# Constant_Voltage_schematic_2022-05-03.net
KiCad netlist of a schematic drawn in Altium Designer
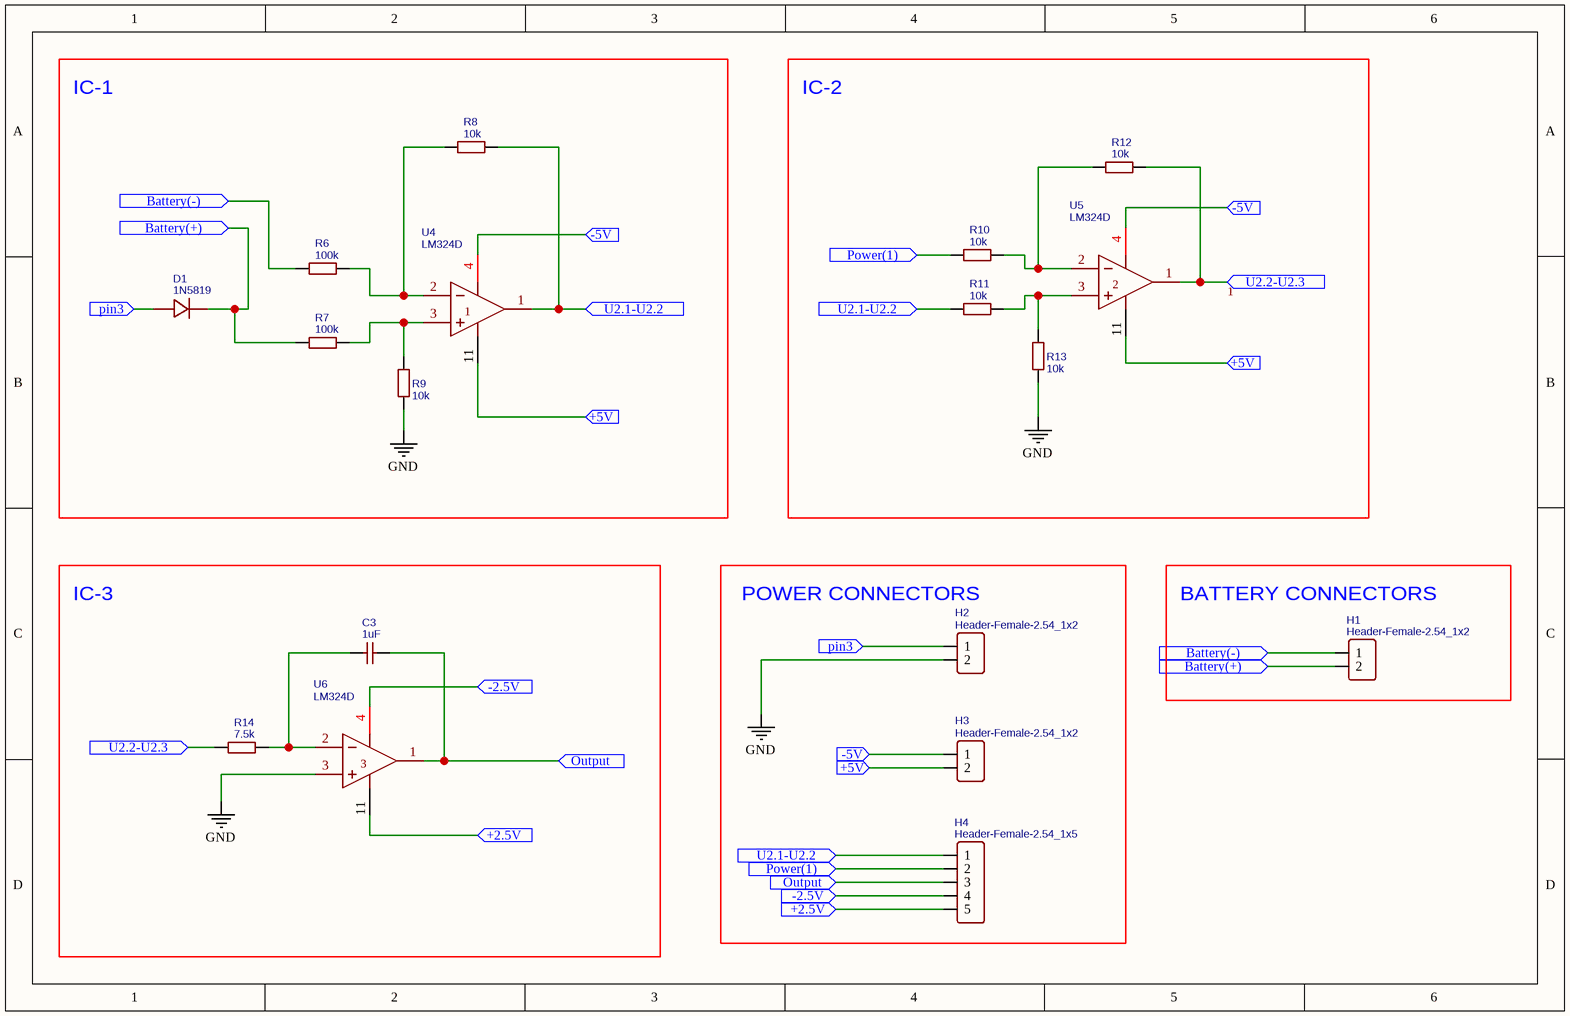
[diagram p0: Constant_Voltage_schematic_2022-05-03.schdoc]

(export (version "E")
  (design (tool "Eeschema 10.0.6"))
  (components
    (comp (ref "C3")
      (value "1uF")
      (fields
        (field (name "BOM_MANUFACTURER PART") "22pf/50V 10%")
        (field (name "BOM_SUPPLIER PART") "C9316")
      )
      (libsource (lib "altium-import") (part "root_0_1uF_"))
    )
    (comp (ref "D1")
      (value "1N5819")
      (fields (field (name "BOM_SUPPLIER PART") "C256527") (field (name "CONTRIBUTOR") "LCSC"))
      (libsource (lib "altium-import") (part "root_2_1N5819_"))
    )
    (comp (ref "H1")
      (value "Header-Female-2.54_1x2")
      (fields
        (field (name "BOM_MANUFACTURER PART") "2.54-1*2PFemale")
        (field (name "BOM_SUPPLIER PART") "C49661")
      )
      (libsource (lib "altium-import") (part "root_0_Header-Female-2.54_1x2_"))
    )
    (comp (ref "H2")
      (value "Header-Female-2.54_1x2")
      (fields
        (field (name "BOM_MANUFACTURER PART") "2.54-1*2PFemale")
        (field (name "BOM_SUPPLIER PART") "C49661")
      )
      (libsource (lib "altium-import") (part "root_0_Header-Female-2.54_1x2_"))
    )
    (comp (ref "H3")
      (value "Header-Female-2.54_1x2")
      (fields
        (field (name "BOM_MANUFACTURER PART") "2.54-1*2PFemale")
        (field (name "BOM_SUPPLIER PART") "C49661")
      )
      (libsource (lib "altium-import") (part "root_0_Header-Female-2.54_1x2_"))
    )
    (comp (ref "H4")
      (value "Header-Female-2.54_1x5")
      (fields
        (field (name "BOM_MANUFACTURER PART") "2.54mm 1*5p Female header")
        (field (name "BOM_SUPPLIER PART") "C50950")
      )
      (libsource (lib "altium-import") (part "root_0_Header-Female-2.54_1x5_"))
    )
    (comp (ref "R6")
      (value "100k")
      (fields
        (field (name "POWER") "1/4W")
        (field (name "TOLERANCE") "±1%")
        (field (name "BOM_SUPPLIER PART") "E57439")
      )
      (libsource (lib "altium-import") (part "root_0_100k_"))
    )
    (comp (ref "R7")
      (value "100k")
      (fields
        (field (name "POWER") "1/4W")
        (field (name "TOLERANCE") "±1%")
        (field (name "BOM_SUPPLIER PART") "E57439")
      )
      (libsource (lib "altium-import") (part "root_0_100k_"))
    )
    (comp (ref "R8")
      (value "10k")
      (fields
        (field (name "POWER") "1/4W")
        (field (name "TOLERANCE") "±1%")
        (field (name "BOM_SUPPLIER PART") "E57439")
      )
      (libsource (lib "altium-import") (part "root_0_10k_"))
    )
    (comp (ref "R9")
      (value "10k")
      (fields
        (field (name "POWER") "1/4W")
        (field (name "TOLERANCE") "±1%")
        (field (name "BOM_SUPPLIER PART") "E57439")
      )
      (libsource (lib "altium-import") (part "root_1_10k_"))
    )
    (comp (ref "R10")
      (value "10k")
      (fields
        (field (name "POWER") "1/4W")
        (field (name "TOLERANCE") "±1%")
        (field (name "BOM_SUPPLIER PART") "E57439")
      )
      (libsource (lib "altium-import") (part "root_0_10k_"))
    )
    (comp (ref "R11")
      (value "10k")
      (fields
        (field (name "POWER") "1/4W")
        (field (name "TOLERANCE") "±1%")
        (field (name "BOM_SUPPLIER PART") "E57439")
      )
      (libsource (lib "altium-import") (part "root_0_10k_"))
    )
    (comp (ref "R12")
      (value "10k")
      (fields
        (field (name "POWER") "1/4W")
        (field (name "TOLERANCE") "±1%")
        (field (name "BOM_SUPPLIER PART") "E57439")
      )
      (libsource (lib "altium-import") (part "root_0_10k_"))
    )
    (comp (ref "R13")
      (value "10k")
      (fields
        (field (name "POWER") "1/4W")
        (field (name "TOLERANCE") "±1%")
        (field (name "BOM_SUPPLIER PART") "E57439")
      )
      (libsource (lib "altium-import") (part "root_1_10k_"))
    )
    (comp (ref "R14")
      (value "7.5k")
      (fields
        (field (name "POWER") "1/4W")
        (field (name "TOLERANCE") "±1%")
        (field (name "BOM_SUPPLIER PART") "E57439")
      )
      (libsource (lib "altium-import") (part "root_0_7.5k_"))
    )
    (comp (ref "U4")
      (value "LM324D")
      (fields
        (field (name "BOM_SUPPLIER PART") "C2935189")
        (field (name "SUBPART_NO") "1")
        (field (name "CONTRIBUTOR") "LCSC")
      )
      (libsource (lib "altium-import") (part "root_0_LM324D_"))
    )
    (comp (ref "U5")
      (value "LM324D")
      (fields
        (field (name "BOM_SUPPLIER PART") "C2935189")
        (field (name "SUBPART_NO") "1")
        (field (name "CONTRIBUTOR") "LCSC")
      )
      (libsource (lib "altium-import") (part "root_0_LM324D_"))
    )
    (comp (ref "U6")
      (value "LM324D")
      (fields
        (field (name "BOM_SUPPLIER PART") "C2935189")
        (field (name "SUBPART_NO") "1")
        (field (name "CONTRIBUTOR") "LCSC")
      )
      (libsource (lib "altium-import") (part "root_0_LM324D_"))
    )
  )
  (nets
    (net (code "1") (name "/+2.5V") (class "Default")
      (node (ref "H4") (pin "5") (pinfunction "5_5") (pintype "passive"))
      (node (ref "U6") (pin "11") (pinfunction "VCC-_11") (pintype "passive"))
    )
    (net (code "2") (name "/+5V") (class "Default")
      (node (ref "H3") (pin "2") (pinfunction "2_2") (pintype "passive"))
      (node (ref "U4") (pin "11") (pinfunction "VCC-_11") (pintype "passive"))
      (node (ref "U5") (pin "11") (pinfunction "VCC-_11") (pintype "passive"))
    )
    (net (code "3") (name "/-2.5V") (class "Default")
      (node (ref "H4") (pin "4") (pinfunction "4_4") (pintype "passive"))
      (node (ref "U6") (pin "4") (pinfunction "VCC+_4") (pintype "passive"))
    )
    (net (code "4") (name "/-5V") (class "Default")
      (node (ref "H3") (pin "1") (pinfunction "1_1") (pintype "passive"))
      (node (ref "U4") (pin "4") (pinfunction "VCC+_4") (pintype "passive"))
      (node (ref "U5") (pin "4") (pinfunction "VCC+_4") (pintype "passive"))
    )
    (net (code "5") (name "/Battery(+)") (class "Default")
      (node (ref "D1") (pin "1") (pinfunction "K_1") (pintype "passive"))
      (node (ref "H1") (pin "2") (pinfunction "2_2") (pintype "passive"))
      (node (ref "R7") (pin "1") (pinfunction "1_1") (pintype "passive"))
    )
    (net (code "6") (name "/Battery(-)") (class "Default")
      (node (ref "H1") (pin "1") (pinfunction "1_1") (pintype "passive"))
      (node (ref "R6") (pin "1") (pinfunction "1_1") (pintype "passive"))
    )
    (net (code "7") (name "/Output") (class "Default")
      (node (ref "C3") (pin "2") (pinfunction "2_2") (pintype "passive"))
      (node (ref "H4") (pin "3") (pinfunction "3_3") (pintype "passive"))
      (node (ref "U6") (pin "1") (pinfunction "OUT1_1") (pintype "passive"))
    )
    (net (code "8") (name "/Power(1)") (class "Default")
      (node (ref "H4") (pin "2") (pinfunction "2_2") (pintype "passive"))
      (node (ref "R10") (pin "1") (pinfunction "1_1") (pintype "passive"))
    )
    (net (code "9") (name "/U2.1-U2.2") (class "Default")
      (node (ref "H4") (pin "1") (pinfunction "1_1") (pintype "passive"))
      (node (ref "R11") (pin "1") (pinfunction "1_1") (pintype "passive"))
      (node (ref "R8") (pin "2") (pinfunction "2_2") (pintype "passive"))
      (node (ref "U4") (pin "1") (pinfunction "OUT1_1") (pintype "passive"))
    )
    (net (code "10") (name "/U2.2-U2.3") (class "Default")
      (node (ref "R12") (pin "2") (pinfunction "2_2") (pintype "passive"))
      (node (ref "R14") (pin "1") (pinfunction "1_1") (pintype "passive"))
      (node (ref "U5") (pin "1") (pinfunction "OUT1_1") (pintype "passive"))
    )
    (net (code "11") (name "/pin3") (class "Default")
      (node (ref "D1") (pin "2") (pinfunction "A_2") (pintype "passive"))
      (node (ref "H2") (pin "1") (pinfunction "1_1") (pintype "passive"))
    )
    (net (code "12") (name "GND") (class "Default")
      (node (ref "H2") (pin "2") (pinfunction "2_2") (pintype "passive"))
      (node (ref "R13") (pin "1") (pinfunction "1_1") (pintype "passive"))
      (node (ref "R9") (pin "1") (pinfunction "1_1") (pintype "passive"))
      (node (ref "U6") (pin "3") (pinfunction "IN1+_3") (pintype "passive"))
    )
    (net (code "13") (name "Net-(U4-IN1+)") (class "Default")
      (node (ref "R7") (pin "2") (pinfunction "2_2") (pintype "passive"))
      (node (ref "R9") (pin "2") (pinfunction "2_2") (pintype "passive"))
      (node (ref "U4") (pin "3") (pinfunction "IN1+_3") (pintype "passive"))
    )
    (net (code "14") (name "Net-(U4-IN1-)") (class "Default")
      (node (ref "R6") (pin "2") (pinfunction "2_2") (pintype "passive"))
      (node (ref "R8") (pin "1") (pinfunction "1_1") (pintype "passive"))
      (node (ref "U4") (pin "2") (pinfunction "IN1-_2") (pintype "passive"))
    )
    (net (code "15") (name "Net-(U5-IN1+)") (class "Default")
      (node (ref "R11") (pin "2") (pinfunction "2_2") (pintype "passive"))
      (node (ref "R13") (pin "2") (pinfunction "2_2") (pintype "passive"))
      (node (ref "U5") (pin "3") (pinfunction "IN1+_3") (pintype "passive"))
    )
    (net (code "16") (name "Net-(U5-IN1-)") (class "Default")
      (node (ref "R10") (pin "2") (pinfunction "2_2") (pintype "passive"))
      (node (ref "R12") (pin "1") (pinfunction "1_1") (pintype "passive"))
      (node (ref "U5") (pin "2") (pinfunction "IN1-_2") (pintype "passive"))
    )
    (net (code "17") (name "Net-(U6-IN1-)") (class "Default")
      (node (ref "C3") (pin "1") (pinfunction "1_1") (pintype "passive"))
      (node (ref "R14") (pin "2") (pinfunction "2_2") (pintype "passive"))
      (node (ref "U6") (pin "2") (pinfunction "IN1-_2") (pintype "passive"))
    )
  )
)
